# esp-prog-SMD.net
KiCad netlist of a schematic drawn in EAGLE
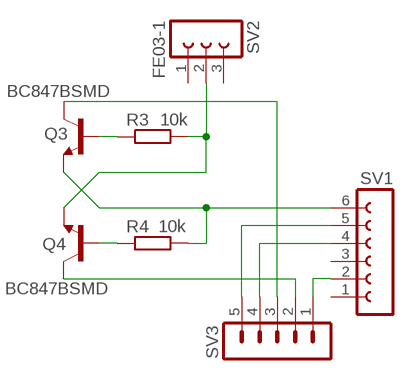
[diagram p0: schematic, sheet 1]

(export (version "E")
  (design (tool "Eeschema 10.0.6"))
  (components
    (comp (ref "Q3")
      (value "BC847BSMD")
      (footprint "eagle-import:SOT23")
      (libsource (lib "eagle-import") (part "BC847SMDB"))
    )
    (comp (ref "Q4")
      (value "BC847BSMD")
      (footprint "eagle-import:SOT23")
      (libsource (lib "eagle-import") (part "BC847SMDB"))
    )
    (comp (ref "R3")
      (value "10k")
      (footprint "eagle-import:R1206")
      (libsource (lib "eagle-import") (part "R-EU_R1206"))
    )
    (comp (ref "R4")
      (value "10k")
      (footprint "eagle-import:R1206")
      (libsource (lib "eagle-import") (part "R-EU_R1206"))
    )
    (comp (ref "SV1")
      (value "FE06-1")
      (footprint "eagle-import:FE06")
      (libsource (lib "eagle-import") (part "FE06-1"))
    )
    (comp (ref "SV2")
      (value "FE03-1")
      (footprint "eagle-import:FE03-1")
      (libsource (lib "eagle-import") (part "FE03-1"))
    )
    (comp (ref "SV3")
      (value "MA05-1")
      (footprint "eagle-import:MA05-1")
      (libsource (lib "eagle-import") (part "MA05-1"))
    )
  )
  (nets
    (net (code "1") (name "Net-(Q3-B)") (class "Default")
      (node (ref "Q3") (pin "1") (pinfunction "B_1") (pintype "passive"))
      (node (ref "R3") (pin "1") (pinfunction "1_1") (pintype "passive"))
    )
    (net (code "2") (name "Net-(Q3-C)") (class "Default")
      (node (ref "Q3") (pin "3") (pinfunction "C_3") (pintype "passive"))
      (node (ref "SV3") (pin "3") (pinfunction "3_3") (pintype "passive"))
    )
    (net (code "3") (name "Net-(Q3-E)") (class "Default")
      (node (ref "Q3") (pin "2") (pinfunction "E_2") (pintype "passive"))
      (node (ref "R4") (pin "2") (pinfunction "2_2") (pintype "passive"))
      (node (ref "SV1") (pin "6") (pinfunction "6_6") (pintype "passive"))
    )
    (net (code "4") (name "Net-(Q4-B)") (class "Default")
      (node (ref "Q4") (pin "1") (pinfunction "B_1") (pintype "passive"))
      (node (ref "R4") (pin "1") (pinfunction "1_1") (pintype "passive"))
    )
    (net (code "5") (name "Net-(Q4-C)") (class "Default")
      (node (ref "Q4") (pin "3") (pinfunction "C_3") (pintype "passive"))
      (node (ref "SV3") (pin "2") (pinfunction "2_2") (pintype "passive"))
    )
    (net (code "6") (name "Net-(Q4-E)") (class "Default")
      (node (ref "Q4") (pin "2") (pinfunction "E_2") (pintype "passive"))
      (node (ref "R3") (pin "2") (pinfunction "2_2") (pintype "passive"))
      (node (ref "SV2") (pin "2") (pinfunction "2_2") (pintype "passive"))
    )
    (net (code "7") (name "Net-(SV1-Pad2)") (class "Default")
      (node (ref "SV1") (pin "2") (pinfunction "2_2") (pintype "passive"))
      (node (ref "SV3") (pin "1") (pinfunction "1_1") (pintype "passive"))
    )
    (net (code "8") (name "Net-(SV1-Pad4)") (class "Default")
      (node (ref "SV1") (pin "4") (pinfunction "4_4") (pintype "passive"))
      (node (ref "SV3") (pin "4") (pinfunction "4_4") (pintype "passive"))
    )
    (net (code "9") (name "Net-(SV1-Pad5)") (class "Default")
      (node (ref "SV1") (pin "5") (pinfunction "5_5") (pintype "passive"))
      (node (ref "SV3") (pin "5") (pinfunction "5_5") (pintype "passive"))
    )
    (net (code "10") (name "unconnected-(SV1-Pad1)") (class "Default")
      (node (ref "SV1") (pin "1") (pinfunction "1_1") (pintype "passive"))
    )
    (net (code "11") (name "unconnected-(SV1-Pad3)") (class "Default")
      (node (ref "SV1") (pin "3") (pinfunction "3_3") (pintype "passive"))
    )
    (net (code "12") (name "unconnected-(SV2-Pad1)") (class "Default")
      (node (ref "SV2") (pin "1") (pinfunction "1_1") (pintype "passive"))
    )
    (net (code "13") (name "unconnected-(SV2-Pad3)") (class "Default")
      (node (ref "SV2") (pin "3") (pinfunction "3_3") (pintype "passive"))
    )
  )
)
